# Encoders.net
KiCad netlist of a schematic drawn in Altium Designer
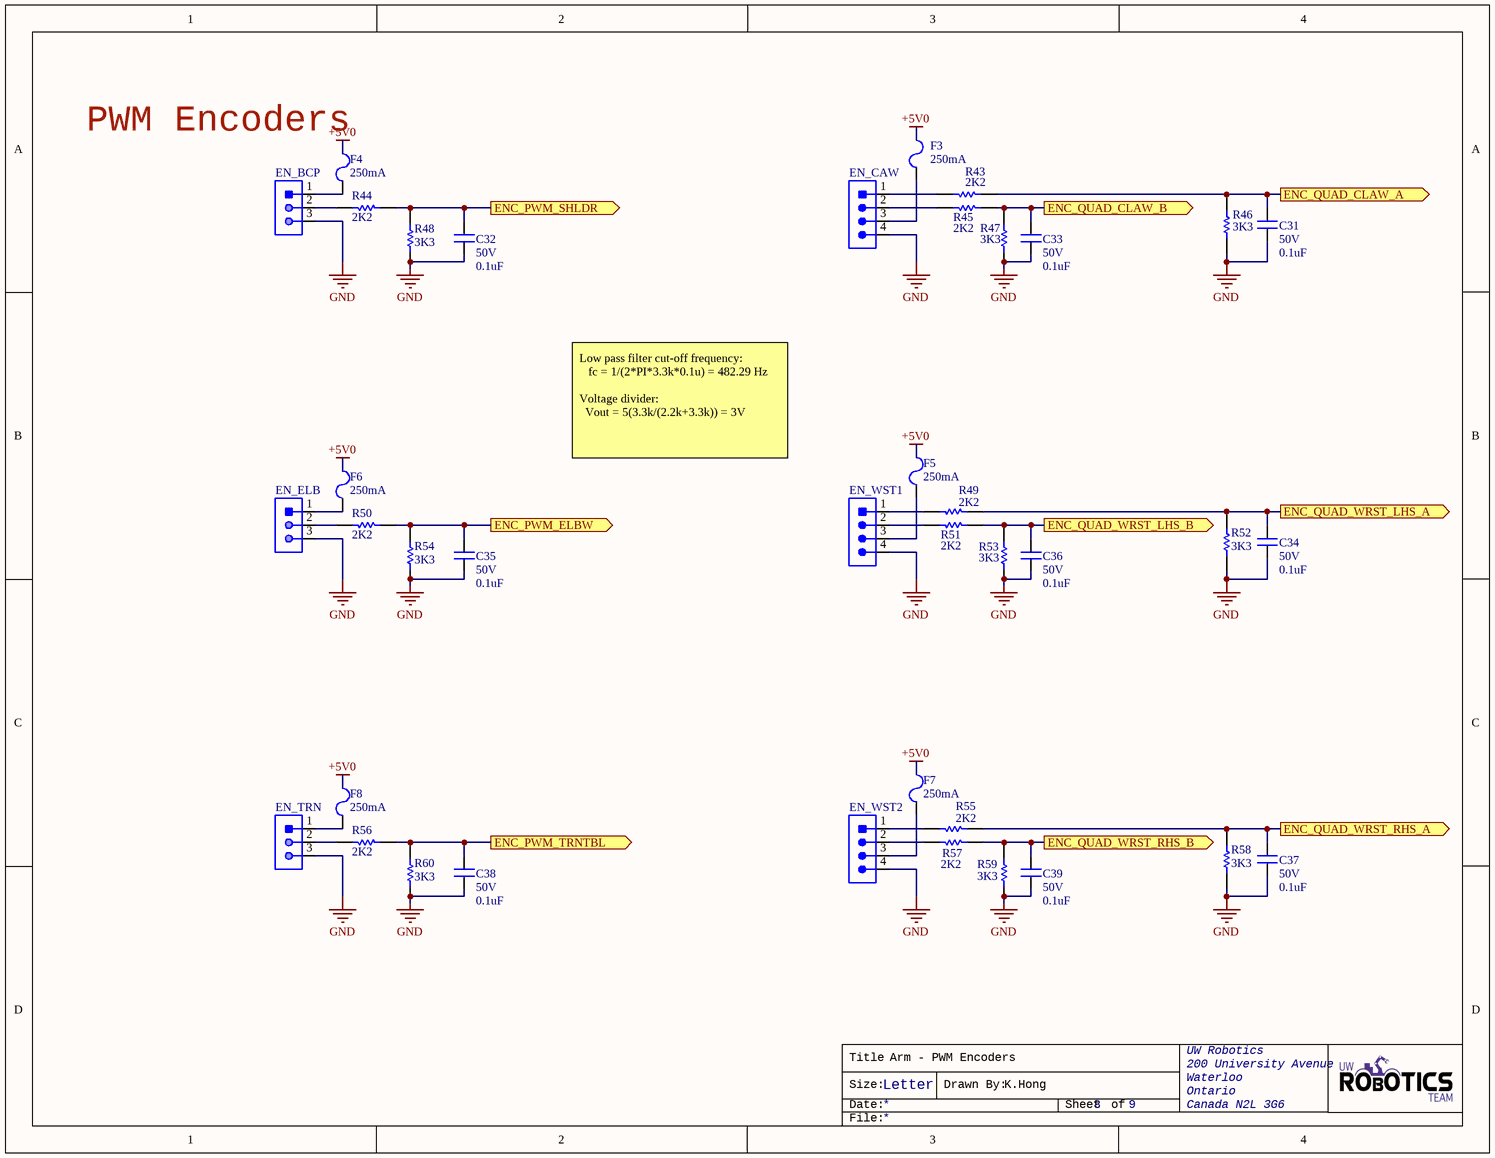
[diagram p0: Encoders.SchDoc]

(export (version "E")
  (design (tool "Eeschema 10.0.6"))
  (components
    (comp (ref "C31")
      (value "0.1uF")
      (footprint "CAPC0603(1608)55_N")
      (description "CAP CER 0.1UF 50V X7R 0603")
      (fields
        (field (name "MPN") "CC0603KRX7R9BB104")
        (field (name "MANUFACTURER") "Yageo")
        (field (name "VOLTAGE RATING") "50V")
      )
      (libsource (lib "UWRT_Schematic_Library_2020") (part "CAP_0.1uF_50V_0603"))
    )
    (comp (ref "C32")
      (value "0.1uF")
      (footprint "CAPC0603(1608)55_N")
      (description "CAP CER 0.1UF 50V X7R 0603")
      (fields
        (field (name "MPN") "CC0603KRX7R9BB104")
        (field (name "MANUFACTURER") "Yageo")
        (field (name "VOLTAGE RATING") "50V")
      )
      (libsource (lib "UWRT_Schematic_Library_2020") (part "CAP_0.1uF_50V_0603"))
    )
    (comp (ref "C33")
      (value "0.1uF")
      (footprint "CAPC0603(1608)55_N")
      (description "CAP CER 0.1UF 50V X7R 0603")
      (fields
        (field (name "MPN") "CC0603KRX7R9BB104")
        (field (name "MANUFACTURER") "Yageo")
        (field (name "VOLTAGE RATING") "50V")
      )
      (libsource (lib "UWRT_Schematic_Library_2020") (part "CAP_0.1uF_50V_0603"))
    )
    (comp (ref "C34")
      (value "0.1uF")
      (footprint "CAPC0603(1608)55_N")
      (description "CAP CER 0.1UF 50V X7R 0603")
      (fields
        (field (name "MPN") "CC0603KRX7R9BB104")
        (field (name "MANUFACTURER") "Yageo")
        (field (name "VOLTAGE RATING") "50V")
      )
      (libsource (lib "UWRT_Schematic_Library_2020") (part "CAP_0.1uF_50V_0603"))
    )
    (comp (ref "C35")
      (value "0.1uF")
      (footprint "CAPC0603(1608)55_N")
      (description "CAP CER 0.1UF 50V X7R 0603")
      (fields
        (field (name "MPN") "CC0603KRX7R9BB104")
        (field (name "MANUFACTURER") "Yageo")
        (field (name "VOLTAGE RATING") "50V")
      )
      (libsource (lib "UWRT_Schematic_Library_2020") (part "CAP_0.1uF_50V_0603"))
    )
    (comp (ref "C36")
      (value "0.1uF")
      (footprint "CAPC0603(1608)55_N")
      (description "CAP CER 0.1UF 50V X7R 0603")
      (fields
        (field (name "MPN") "CC0603KRX7R9BB104")
        (field (name "MANUFACTURER") "Yageo")
        (field (name "VOLTAGE RATING") "50V")
      )
      (libsource (lib "UWRT_Schematic_Library_2020") (part "CAP_0.1uF_50V_0603"))
    )
    (comp (ref "C37")
      (value "0.1uF")
      (footprint "CAPC0603(1608)55_N")
      (description "CAP CER 0.1UF 50V X7R 0603")
      (fields
        (field (name "MPN") "CC0603KRX7R9BB104")
        (field (name "MANUFACTURER") "Yageo")
        (field (name "VOLTAGE RATING") "50V")
      )
      (libsource (lib "UWRT_Schematic_Library_2020") (part "CAP_0.1uF_50V_0603"))
    )
    (comp (ref "C38")
      (value "0.1uF")
      (footprint "CAPC0603(1608)55_N")
      (description "CAP CER 0.1UF 50V X7R 0603")
      (fields
        (field (name "MPN") "CC0603KRX7R9BB104")
        (field (name "MANUFACTURER") "Yageo")
        (field (name "VOLTAGE RATING") "50V")
      )
      (libsource (lib "UWRT_Schematic_Library_2020") (part "CAP_0.1uF_50V_0603"))
    )
    (comp (ref "C39")
      (value "0.1uF")
      (footprint "CAPC0603(1608)55_N")
      (description "CAP CER 0.1UF 50V X7R 0603")
      (fields
        (field (name "MPN") "CC0603KRX7R9BB104")
        (field (name "MANUFACTURER") "Yageo")
        (field (name "VOLTAGE RATING") "50V")
      )
      (libsource (lib "UWRT_Schematic_Library_2020") (part "CAP_0.1uF_50V_0603"))
    )
    (comp (ref "EN_BCP")
      (value "CON_3M_SM4")
      (footprint "JST-B3B-SM4-TB")
      (description "CONN HEADER SMD 3POS 2MM")
      (fields
        (field (name "MANUFACTURER") "JST")
        (field (name "MANUFACTURER PART NUMBER") "B3B-PH-SM4-TB(LF)(SN)")
      )
      (libsource (lib "UWRT_Schematic_Library_2020") (part "CON_3M_SM4"))
    )
    (comp (ref "EN_CAW")
      (value "CON_4M_SM4")
      (footprint "JST-B4B-SM4-TB")
      (description "CONN HEADER SMD 4POS 2MM")
      (fields
        (field (name "MANUFACTURER") "JST")
        (field (name "MANUFACTURER PART NUMBER") "B4B-PH-SM4-TB(LF)(SN)")
      )
      (libsource (lib "UWRT_Schematic_Library_2020") (part "CON_4M_SM4"))
    )
    (comp (ref "EN_ELB")
      (value "CON_3M_SM4")
      (footprint "JST-B3B-SM4-TB")
      (description "CONN HEADER SMD 3POS 2MM")
      (fields
        (field (name "MANUFACTURER") "JST")
        (field (name "MANUFACTURER PART NUMBER") "B3B-PH-SM4-TB(LF)(SN)")
      )
      (libsource (lib "UWRT_Schematic_Library_2020") (part "CON_3M_SM4"))
    )
    (comp (ref "EN_TRN")
      (value "CON_3M_SM4")
      (footprint "JST-B3B-SM4-TB")
      (description "CONN HEADER SMD 3POS 2MM")
      (fields
        (field (name "MANUFACTURER") "JST")
        (field (name "MANUFACTURER PART NUMBER") "B3B-PH-SM4-TB(LF)(SN)")
      )
      (libsource (lib "UWRT_Schematic_Library_2020") (part "CON_3M_SM4"))
    )
    (comp (ref "EN_WST1")
      (value "CON_4M_SM4")
      (footprint "JST-B4B-SM4-TB")
      (description "CONN HEADER SMD 4POS 2MM")
      (fields
        (field (name "MANUFACTURER") "JST")
        (field (name "MANUFACTURER PART NUMBER") "B4B-PH-SM4-TB(LF)(SN)")
      )
      (libsource (lib "UWRT_Schematic_Library_2020") (part "CON_4M_SM4"))
    )
    (comp (ref "EN_WST2")
      (value "CON_4M_SM4")
      (footprint "JST-B4B-SM4-TB")
      (description "CONN HEADER SMD 4POS 2MM")
      (fields
        (field (name "MANUFACTURER") "JST")
        (field (name "MANUFACTURER PART NUMBER") "B4B-PH-SM4-TB(LF)(SN)")
      )
      (libsource (lib "UWRT_Schematic_Library_2020") (part "CON_4M_SM4"))
    )
    (comp (ref "F3")
      (value "FUSE_250mA_0603")
      (footprint "FUSE_0603")
      (description "FUSE SMD 250mA 32V")
      (fields (field (name "CURRENT RATING") "250mA"))
      (libsource (lib "UWRT_Schematic_Library_2020") (part "FUSE_250mA_0603"))
    )
    (comp (ref "F4")
      (value "FUSE_250mA_0603")
      (footprint "FUSE_0603")
      (description "FUSE SMD 250mA 32V")
      (fields (field (name "CURRENT RATING") "250mA"))
      (libsource (lib "UWRT_Schematic_Library_2020") (part "FUSE_250mA_0603"))
    )
    (comp (ref "F5")
      (value "FUSE_250mA_0603")
      (footprint "FUSE_0603")
      (description "FUSE SMD 250mA 32V")
      (fields (field (name "CURRENT RATING") "250mA"))
      (libsource (lib "UWRT_Schematic_Library_2020") (part "FUSE_250mA_0603"))
    )
    (comp (ref "F6")
      (value "FUSE_250mA_0603")
      (footprint "FUSE_0603")
      (description "FUSE SMD 250mA 32V")
      (fields (field (name "CURRENT RATING") "250mA"))
      (libsource (lib "UWRT_Schematic_Library_2020") (part "FUSE_250mA_0603"))
    )
    (comp (ref "F7")
      (value "FUSE_250mA_0603")
      (footprint "FUSE_0603")
      (description "FUSE SMD 250mA 32V")
      (fields (field (name "CURRENT RATING") "250mA"))
      (libsource (lib "UWRT_Schematic_Library_2020") (part "FUSE_250mA_0603"))
    )
    (comp (ref "F8")
      (value "FUSE_250mA_0603")
      (footprint "FUSE_0603")
      (description "FUSE SMD 250mA 32V")
      (fields (field (name "CURRENT RATING") "250mA"))
      (libsource (lib "UWRT_Schematic_Library_2020") (part "FUSE_250mA_0603"))
    )
    (comp (ref "R43")
      (value "2K2")
      (footprint "RESC0603(1608)_N")
      (description "RES SMD 2.2K OHM 1% 1/10W 0603")
      (fields (field (name "MANUFACTURER") "Yageo") (field (name "TOLERANCE") "1%"))
      (libsource (lib "UWRT_Schematic_Library_2020") (part "RES_2K2_0603"))
    )
    (comp (ref "R44")
      (value "2K2")
      (footprint "RESC0603(1608)_N")
      (description "RES SMD 2.2K OHM 1% 1/10W 0603")
      (fields (field (name "MANUFACTURER") "Yageo") (field (name "TOLERANCE") "1%"))
      (libsource (lib "UWRT_Schematic_Library_2020") (part "RES_2K2_0603"))
    )
    (comp (ref "R45")
      (value "2K2")
      (footprint "RESC0603(1608)_N")
      (description "RES SMD 2.2K OHM 1% 1/10W 0603")
      (fields (field (name "MANUFACTURER") "Yageo") (field (name "TOLERANCE") "1%"))
      (libsource (lib "UWRT_Schematic_Library_2020") (part "RES_2K2_0603"))
    )
    (comp (ref "R46")
      (value "3K3")
      (footprint "RESC0603(1608)_N")
      (description "RES SMD 3.3K OHM 5% 1/10W 0603")
      (fields (field (name "MANUFACTURER") "Yageo") (field (name "TOLERANCE") "5%"))
      (libsource (lib "UWRT_Schematic_Library_2020") (part "RES_3K3_0603"))
    )
    (comp (ref "R47")
      (value "3K3")
      (footprint "RESC0603(1608)_N")
      (description "RES SMD 3.3K OHM 5% 1/10W 0603")
      (fields (field (name "MANUFACTURER") "Yageo") (field (name "TOLERANCE") "5%"))
      (libsource (lib "UWRT_Schematic_Library_2020") (part "RES_3K3_0603"))
    )
    (comp (ref "R48")
      (value "3K3")
      (footprint "RESC0603(1608)_N")
      (description "RES SMD 3.3K OHM 5% 1/10W 0603")
      (fields (field (name "MANUFACTURER") "Yageo") (field (name "TOLERANCE") "5%"))
      (libsource (lib "UWRT_Schematic_Library_2020") (part "RES_3K3_0603"))
    )
    (comp (ref "R49")
      (value "2K2")
      (footprint "RESC0603(1608)_N")
      (description "RES SMD 2.2K OHM 1% 1/10W 0603")
      (fields (field (name "MANUFACTURER") "Yageo") (field (name "TOLERANCE") "1%"))
      (libsource (lib "UWRT_Schematic_Library_2020") (part "RES_2K2_0603"))
    )
    (comp (ref "R50")
      (value "2K2")
      (footprint "RESC0603(1608)_N")
      (description "RES SMD 2.2K OHM 1% 1/10W 0603")
      (fields (field (name "MANUFACTURER") "Yageo") (field (name "TOLERANCE") "1%"))
      (libsource (lib "UWRT_Schematic_Library_2020") (part "RES_2K2_0603"))
    )
    (comp (ref "R51")
      (value "2K2")
      (footprint "RESC0603(1608)_N")
      (description "RES SMD 2.2K OHM 1% 1/10W 0603")
      (fields (field (name "MANUFACTURER") "Yageo") (field (name "TOLERANCE") "1%"))
      (libsource (lib "UWRT_Schematic_Library_2020") (part "RES_2K2_0603"))
    )
    (comp (ref "R52")
      (value "3K3")
      (footprint "RESC0603(1608)_N")
      (description "RES SMD 3.3K OHM 5% 1/10W 0603")
      (fields (field (name "MANUFACTURER") "Yageo") (field (name "TOLERANCE") "5%"))
      (libsource (lib "UWRT_Schematic_Library_2020") (part "RES_3K3_0603"))
    )
    (comp (ref "R53")
      (value "3K3")
      (footprint "RESC0603(1608)_N")
      (description "RES SMD 3.3K OHM 5% 1/10W 0603")
      (fields (field (name "MANUFACTURER") "Yageo") (field (name "TOLERANCE") "5%"))
      (libsource (lib "UWRT_Schematic_Library_2020") (part "RES_3K3_0603"))
    )
    (comp (ref "R54")
      (value "3K3")
      (footprint "RESC0603(1608)_N")
      (description "RES SMD 3.3K OHM 5% 1/10W 0603")
      (fields (field (name "MANUFACTURER") "Yageo") (field (name "TOLERANCE") "5%"))
      (libsource (lib "UWRT_Schematic_Library_2020") (part "RES_3K3_0603"))
    )
    (comp (ref "R55")
      (value "2K2")
      (footprint "RESC0603(1608)_N")
      (description "RES SMD 2.2K OHM 1% 1/10W 0603")
      (fields (field (name "MANUFACTURER") "Yageo") (field (name "TOLERANCE") "1%"))
      (libsource (lib "UWRT_Schematic_Library_2020") (part "RES_2K2_0603"))
    )
    (comp (ref "R56")
      (value "2K2")
      (footprint "RESC0603(1608)_N")
      (description "RES SMD 2.2K OHM 1% 1/10W 0603")
      (fields (field (name "MANUFACTURER") "Yageo") (field (name "TOLERANCE") "1%"))
      (libsource (lib "UWRT_Schematic_Library_2020") (part "RES_2K2_0603"))
    )
    (comp (ref "R57")
      (value "2K2")
      (footprint "RESC0603(1608)_N")
      (description "RES SMD 2.2K OHM 1% 1/10W 0603")
      (fields (field (name "MANUFACTURER") "Yageo") (field (name "TOLERANCE") "1%"))
      (libsource (lib "UWRT_Schematic_Library_2020") (part "RES_2K2_0603"))
    )
    (comp (ref "R58")
      (value "3K3")
      (footprint "RESC0603(1608)_N")
      (description "RES SMD 3.3K OHM 5% 1/10W 0603")
      (fields (field (name "MANUFACTURER") "Yageo") (field (name "TOLERANCE") "5%"))
      (libsource (lib "UWRT_Schematic_Library_2020") (part "RES_3K3_0603"))
    )
    (comp (ref "R59")
      (value "3K3")
      (footprint "RESC0603(1608)_N")
      (description "RES SMD 3.3K OHM 5% 1/10W 0603")
      (fields (field (name "MANUFACTURER") "Yageo") (field (name "TOLERANCE") "5%"))
      (libsource (lib "UWRT_Schematic_Library_2020") (part "RES_3K3_0603"))
    )
    (comp (ref "R60")
      (value "3K3")
      (footprint "RESC0603(1608)_N")
      (description "RES SMD 3.3K OHM 5% 1/10W 0603")
      (fields (field (name "MANUFACTURER") "Yageo") (field (name "TOLERANCE") "5%"))
      (libsource (lib "UWRT_Schematic_Library_2020") (part "RES_3K3_0603"))
    )
  )
  (nets
    (net (code "1") (name "+5V0") (class "Default")
      (node (ref "F3") (pin "2") (pinfunction "2_2") (pintype "passive"))
      (node (ref "F4") (pin "2") (pinfunction "2_2") (pintype "passive"))
      (node (ref "F5") (pin "2") (pinfunction "2_2") (pintype "passive"))
      (node (ref "F6") (pin "2") (pinfunction "2_2") (pintype "passive"))
      (node (ref "F7") (pin "2") (pinfunction "2_2") (pintype "passive"))
      (node (ref "F8") (pin "2") (pinfunction "2_2") (pintype "passive"))
    )
    (net (code "2") (name "/ENC_PWM_ELBW") (class "Default")
      (node (ref "C35") (pin "2") (pinfunction "2_2") (pintype "passive"))
      (node (ref "R50") (pin "1") (pinfunction "1_1") (pintype "passive"))
      (node (ref "R54") (pin "2") (pinfunction "2_2") (pintype "passive"))
    )
    (net (code "3") (name "/ENC_PWM_SHLDR") (class "Default")
      (node (ref "C32") (pin "2") (pinfunction "2_2") (pintype "passive"))
      (node (ref "R44") (pin "1") (pinfunction "1_1") (pintype "passive"))
      (node (ref "R48") (pin "2") (pinfunction "2_2") (pintype "passive"))
    )
    (net (code "4") (name "/ENC_PWM_TRNTBL") (class "Default")
      (node (ref "C38") (pin "2") (pinfunction "2_2") (pintype "passive"))
      (node (ref "R56") (pin "1") (pinfunction "1_1") (pintype "passive"))
      (node (ref "R60") (pin "2") (pinfunction "2_2") (pintype "passive"))
    )
    (net (code "5") (name "/ENC_QUAD_CLAW_A") (class "Default")
      (node (ref "C31") (pin "2") (pinfunction "2_2") (pintype "passive"))
      (node (ref "R43") (pin "1") (pinfunction "1_1") (pintype "passive"))
      (node (ref "R46") (pin "2") (pinfunction "2_2") (pintype "passive"))
    )
    (net (code "6") (name "/ENC_QUAD_CLAW_B") (class "Default")
      (node (ref "C33") (pin "2") (pinfunction "2_2") (pintype "passive"))
      (node (ref "R45") (pin "1") (pinfunction "1_1") (pintype "passive"))
      (node (ref "R47") (pin "2") (pinfunction "2_2") (pintype "passive"))
    )
    (net (code "7") (name "/ENC_QUAD_WRST_LHS_A") (class "Default")
      (node (ref "C34") (pin "2") (pinfunction "2_2") (pintype "passive"))
      (node (ref "R49") (pin "1") (pinfunction "1_1") (pintype "passive"))
      (node (ref "R52") (pin "2") (pinfunction "2_2") (pintype "passive"))
    )
    (net (code "8") (name "/ENC_QUAD_WRST_LHS_B") (class "Default")
      (node (ref "C36") (pin "2") (pinfunction "2_2") (pintype "passive"))
      (node (ref "R51") (pin "1") (pinfunction "1_1") (pintype "passive"))
      (node (ref "R53") (pin "2") (pinfunction "2_2") (pintype "passive"))
    )
    (net (code "9") (name "/ENC_QUAD_WRST_RHS_A") (class "Default")
      (node (ref "C37") (pin "2") (pinfunction "2_2") (pintype "passive"))
      (node (ref "R55") (pin "1") (pinfunction "1_1") (pintype "passive"))
      (node (ref "R58") (pin "2") (pinfunction "2_2") (pintype "passive"))
    )
    (net (code "10") (name "/ENC_QUAD_WRST_RHS_B") (class "Default")
      (node (ref "C39") (pin "2") (pinfunction "2_2") (pintype "passive"))
      (node (ref "R57") (pin "1") (pinfunction "1_1") (pintype "passive"))
      (node (ref "R59") (pin "2") (pinfunction "2_2") (pintype "passive"))
    )
    (net (code "11") (name "GND") (class "Default")
      (node (ref "C31") (pin "1") (pinfunction "1_1") (pintype "passive"))
      (node (ref "C32") (pin "1") (pinfunction "1_1") (pintype "passive"))
      (node (ref "C33") (pin "1") (pinfunction "1_1") (pintype "passive"))
      (node (ref "C34") (pin "1") (pinfunction "1_1") (pintype "passive"))
      (node (ref "C35") (pin "1") (pinfunction "1_1") (pintype "passive"))
      (node (ref "C36") (pin "1") (pinfunction "1_1") (pintype "passive"))
      (node (ref "C37") (pin "1") (pinfunction "1_1") (pintype "passive"))
      (node (ref "C38") (pin "1") (pinfunction "1_1") (pintype "passive"))
      (node (ref "C39") (pin "1") (pinfunction "1_1") (pintype "passive"))
      (node (ref "EN_BCP") (pin "3") (pinfunction "3_3") (pintype "passive"))
      (node (ref "EN_CAW") (pin "4") (pinfunction "4_4") (pintype "passive"))
      (node (ref "EN_ELB") (pin "3") (pinfunction "3_3") (pintype "passive"))
      (node (ref "EN_TRN") (pin "3") (pinfunction "3_3") (pintype "passive"))
      (node (ref "EN_WST1") (pin "4") (pinfunction "4_4") (pintype "passive"))
      (node (ref "EN_WST2") (pin "4") (pinfunction "4_4") (pintype "passive"))
      (node (ref "R46") (pin "1") (pinfunction "1_1") (pintype "passive"))
      (node (ref "R47") (pin "1") (pinfunction "1_1") (pintype "passive"))
      (node (ref "R48") (pin "1") (pinfunction "1_1") (pintype "passive"))
      (node (ref "R52") (pin "1") (pinfunction "1_1") (pintype "passive"))
      (node (ref "R53") (pin "1") (pinfunction "1_1") (pintype "passive"))
      (node (ref "R54") (pin "1") (pinfunction "1_1") (pintype "passive"))
      (node (ref "R58") (pin "1") (pinfunction "1_1") (pintype "passive"))
      (node (ref "R59") (pin "1") (pinfunction "1_1") (pintype "passive"))
      (node (ref "R60") (pin "1") (pinfunction "1_1") (pintype "passive"))
    )
    (net (code "12") (name "Net-(EN_BCP-Pad1)") (class "Default")
      (node (ref "EN_BCP") (pin "1") (pinfunction "1_1") (pintype "passive"))
      (node (ref "F4") (pin "1") (pinfunction "1_1") (pintype "passive"))
    )
    (net (code "13") (name "Net-(EN_BCP-Pad2)") (class "Default")
      (node (ref "EN_BCP") (pin "2") (pinfunction "2_2") (pintype "passive"))
      (node (ref "R44") (pin "2") (pinfunction "2_2") (pintype "passive"))
    )
    (net (code "14") (name "Net-(EN_CAW-Pad1)") (class "Default")
      (node (ref "EN_CAW") (pin "1") (pinfunction "1_1") (pintype "passive"))
      (node (ref "R43") (pin "2") (pinfunction "2_2") (pintype "passive"))
    )
    (net (code "15") (name "Net-(EN_CAW-Pad2)") (class "Default")
      (node (ref "EN_CAW") (pin "2") (pinfunction "2_2") (pintype "passive"))
      (node (ref "R45") (pin "2") (pinfunction "2_2") (pintype "passive"))
    )
    (net (code "16") (name "Net-(EN_CAW-Pad3)") (class "Default")
      (node (ref "EN_CAW") (pin "3") (pinfunction "3_3") (pintype "passive"))
      (node (ref "F3") (pin "1") (pinfunction "1_1") (pintype "passive"))
    )
    (net (code "17") (name "Net-(EN_ELB-Pad1)") (class "Default")
      (node (ref "EN_ELB") (pin "1") (pinfunction "1_1") (pintype "passive"))
      (node (ref "F6") (pin "1") (pinfunction "1_1") (pintype "passive"))
    )
    (net (code "18") (name "Net-(EN_ELB-Pad2)") (class "Default")
      (node (ref "EN_ELB") (pin "2") (pinfunction "2_2") (pintype "passive"))
      (node (ref "R50") (pin "2") (pinfunction "2_2") (pintype "passive"))
    )
    (net (code "19") (name "Net-(EN_TRN-Pad1)") (class "Default")
      (node (ref "EN_TRN") (pin "1") (pinfunction "1_1") (pintype "passive"))
      (node (ref "F8") (pin "1") (pinfunction "1_1") (pintype "passive"))
    )
    (net (code "20") (name "Net-(EN_TRN-Pad2)") (class "Default")
      (node (ref "EN_TRN") (pin "2") (pinfunction "2_2") (pintype "passive"))
      (node (ref "R56") (pin "2") (pinfunction "2_2") (pintype "passive"))
    )
    (net (code "21") (name "Net-(EN_WST1-Pad1)") (class "Default")
      (node (ref "EN_WST1") (pin "1") (pinfunction "1_1") (pintype "passive"))
      (node (ref "R49") (pin "2") (pinfunction "2_2") (pintype "passive"))
    )
    (net (code "22") (name "Net-(EN_WST1-Pad2)") (class "Default")
      (node (ref "EN_WST1") (pin "2") (pinfunction "2_2") (pintype "passive"))
      (node (ref "R51") (pin "2") (pinfunction "2_2") (pintype "passive"))
    )
    (net (code "23") (name "Net-(EN_WST1-Pad3)") (class "Default")
      (node (ref "EN_WST1") (pin "3") (pinfunction "3_3") (pintype "passive"))
      (node (ref "F5") (pin "1") (pinfunction "1_1") (pintype "passive"))
    )
    (net (code "24") (name "Net-(EN_WST2-Pad1)") (class "Default")
      (node (ref "EN_WST2") (pin "1") (pinfunction "1_1") (pintype "passive"))
      (node (ref "R55") (pin "2") (pinfunction "2_2") (pintype "passive"))
    )
    (net (code "25") (name "Net-(EN_WST2-Pad2)") (class "Default")
      (node (ref "EN_WST2") (pin "2") (pinfunction "2_2") (pintype "passive"))
      (node (ref "R57") (pin "2") (pinfunction "2_2") (pintype "passive"))
    )
    (net (code "26") (name "Net-(EN_WST2-Pad3)") (class "Default")
      (node (ref "EN_WST2") (pin "3") (pinfunction "3_3") (pintype "passive"))
      (node (ref "F7") (pin "1") (pinfunction "1_1") (pintype "passive"))
    )
  )
)
